# elka.net
KiCad netlist of a schematic drawn in EAGLE
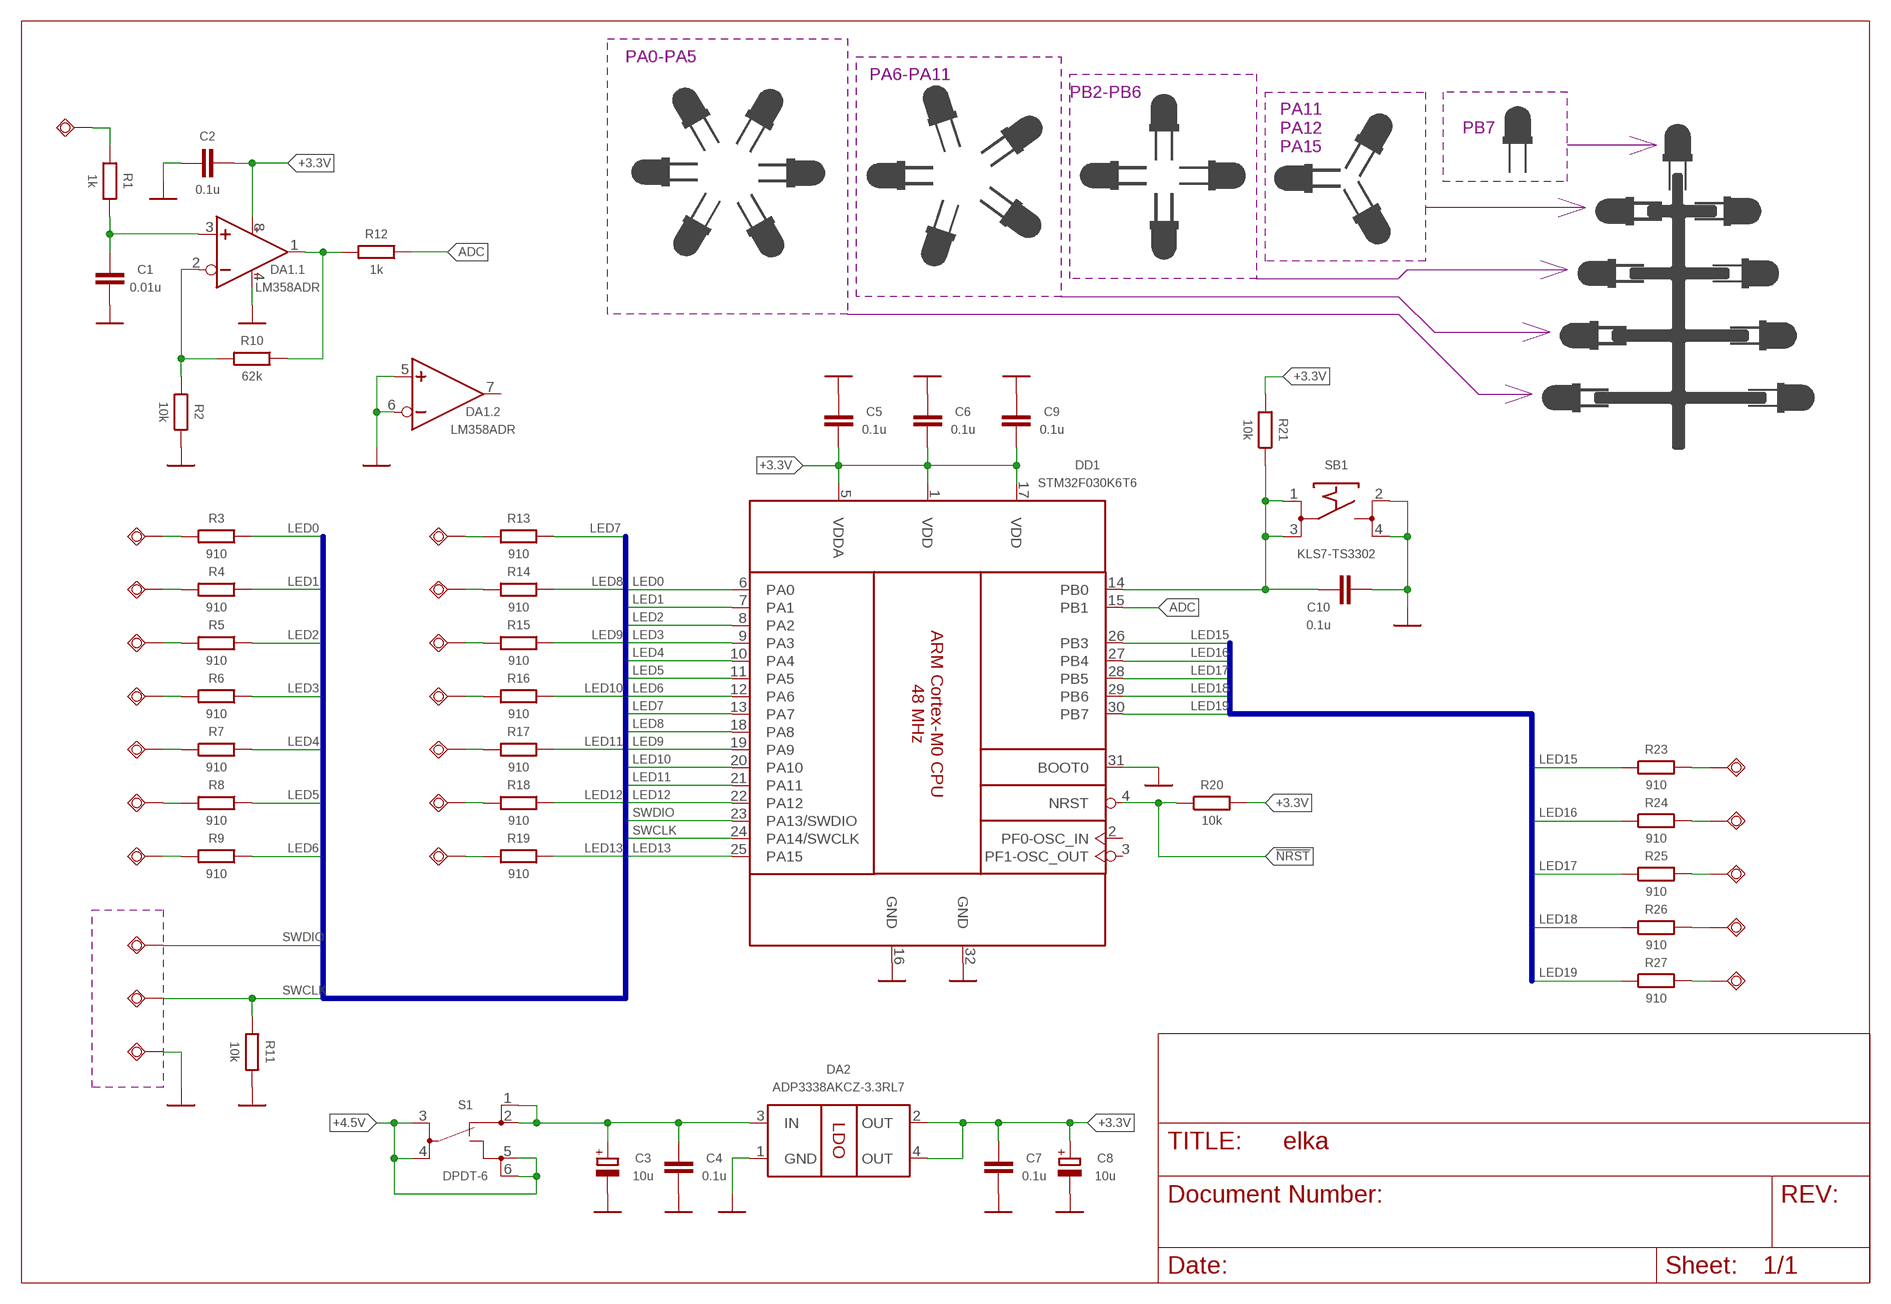
[diagram p0: schematic, sheet 1]

(export (version "E")
  (design (tool "Eeschema 10.0.6"))
  (components
    (comp (ref "C1")
      (value "0.01u")
      (footprint "eagle-import:SMD0603")
      (libsource (lib "eagle-import") (part "C0603"))
    )
    (comp (ref "C2")
      (value "0.1u")
      (footprint "eagle-import:SMD0603")
      (libsource (lib "eagle-import") (part "C0603"))
    )
    (comp (ref "C3")
      (value "10u")
      (footprint "eagle-import:SMC_B")
      (libsource (lib "eagle-import") (part "CPOLSMC_B"))
    )
    (comp (ref "C4")
      (value "0.1u")
      (footprint "eagle-import:SMD0603")
      (libsource (lib "eagle-import") (part "C0603"))
    )
    (comp (ref "C5")
      (value "0.1u")
      (footprint "eagle-import:SMD0603")
      (libsource (lib "eagle-import") (part "C0603"))
    )
    (comp (ref "C6")
      (value "0.1u")
      (footprint "eagle-import:SMD0603")
      (libsource (lib "eagle-import") (part "C0603"))
    )
    (comp (ref "C7")
      (value "0.1u")
      (footprint "eagle-import:SMD0603")
      (libsource (lib "eagle-import") (part "C0603"))
    )
    (comp (ref "C8")
      (value "10u")
      (footprint "eagle-import:SMC_B")
      (libsource (lib "eagle-import") (part "CPOLSMC_B"))
    )
    (comp (ref "C9")
      (value "0.1u")
      (footprint "eagle-import:SMD0603")
      (libsource (lib "eagle-import") (part "C0603"))
    )
    (comp (ref "C10")
      (value "0.1u")
      (footprint "eagle-import:SMD0603")
      (libsource (lib "eagle-import") (part "C0603"))
    )
    (comp (ref "DA1")
      (value "LM358ADR")
      (footprint "eagle-import:SOIC8")
      (libsource (lib "eagle-import") (part "LM358ADR"))
    )
    (comp (ref "DA2")
      (value "ADP3338AKCZ-3.3RL7")
      (footprint "eagle-import:SOT223-W")
      (libsource (lib "eagle-import") (part "ADP3338AKCZ-3.3RL7"))
    )
    (comp (ref "DD1")
      (value "STM32F030K6T6")
      (footprint "eagle-import:LQFP32")
      (libsource (lib "eagle-import") (part "STM32F030K6T6"))
    )
    (comp (ref "R1")
      (value "1k")
      (footprint "eagle-import:SMD0603")
      (libsource (lib "eagle-import") (part "R0603"))
    )
    (comp (ref "R2")
      (value "10k")
      (footprint "eagle-import:SMD0603")
      (libsource (lib "eagle-import") (part "R0603"))
    )
    (comp (ref "R3")
      (value "910")
      (footprint "eagle-import:SMD0603")
      (libsource (lib "eagle-import") (part "R0603"))
    )
    (comp (ref "R4")
      (value "910")
      (footprint "eagle-import:SMD0603")
      (libsource (lib "eagle-import") (part "R0603"))
    )
    (comp (ref "R5")
      (value "910")
      (footprint "eagle-import:SMD0603")
      (libsource (lib "eagle-import") (part "R0603"))
    )
    (comp (ref "R6")
      (value "910")
      (footprint "eagle-import:SMD0603")
      (libsource (lib "eagle-import") (part "R0603"))
    )
    (comp (ref "R7")
      (value "910")
      (footprint "eagle-import:SMD0603")
      (libsource (lib "eagle-import") (part "R0603"))
    )
    (comp (ref "R8")
      (value "910")
      (footprint "eagle-import:SMD0603")
      (libsource (lib "eagle-import") (part "R0603"))
    )
    (comp (ref "R9")
      (value "910")
      (footprint "eagle-import:SMD0603")
      (libsource (lib "eagle-import") (part "R0603"))
    )
    (comp (ref "R10")
      (value "62k")
      (footprint "eagle-import:SMD0603")
      (libsource (lib "eagle-import") (part "R0603"))
    )
    (comp (ref "R11")
      (value "10k")
      (footprint "eagle-import:SMD0603")
      (libsource (lib "eagle-import") (part "R0603"))
    )
    (comp (ref "R12")
      (value "1k")
      (footprint "eagle-import:SMD0603")
      (libsource (lib "eagle-import") (part "R0603"))
    )
    (comp (ref "R13")
      (value "910")
      (footprint "eagle-import:SMD0603")
      (libsource (lib "eagle-import") (part "R0603"))
    )
    (comp (ref "R14")
      (value "910")
      (footprint "eagle-import:SMD0603")
      (libsource (lib "eagle-import") (part "R0603"))
    )
    (comp (ref "R15")
      (value "910")
      (footprint "eagle-import:SMD0603")
      (libsource (lib "eagle-import") (part "R0603"))
    )
    (comp (ref "R16")
      (value "910")
      (footprint "eagle-import:SMD0603")
      (libsource (lib "eagle-import") (part "R0603"))
    )
    (comp (ref "R17")
      (value "910")
      (footprint "eagle-import:SMD0603")
      (libsource (lib "eagle-import") (part "R0603"))
    )
    (comp (ref "R18")
      (value "910")
      (footprint "eagle-import:SMD0603")
      (libsource (lib "eagle-import") (part "R0603"))
    )
    (comp (ref "R19")
      (value "910")
      (footprint "eagle-import:SMD0603")
      (libsource (lib "eagle-import") (part "R0603"))
    )
    (comp (ref "R20")
      (value "10k")
      (footprint "eagle-import:SMD0603")
      (libsource (lib "eagle-import") (part "R0603"))
    )
    (comp (ref "R21")
      (value "10k")
      (footprint "eagle-import:SMD0603")
      (libsource (lib "eagle-import") (part "R0603"))
    )
    (comp (ref "R23")
      (value "910")
      (footprint "eagle-import:SMD0603")
      (libsource (lib "eagle-import") (part "R0603"))
    )
    (comp (ref "R24")
      (value "910")
      (footprint "eagle-import:SMD0603")
      (libsource (lib "eagle-import") (part "R0603"))
    )
    (comp (ref "R25")
      (value "910")
      (footprint "eagle-import:SMD0603")
      (libsource (lib "eagle-import") (part "R0603"))
    )
    (comp (ref "R26")
      (value "910")
      (footprint "eagle-import:SMD0603")
      (libsource (lib "eagle-import") (part "R0603"))
    )
    (comp (ref "R27")
      (value "910")
      (footprint "eagle-import:SMD0603")
      (libsource (lib "eagle-import") (part "R0603"))
    )
    (comp (ref "S1")
      (value "DPDT-6")
      (footprint "eagle-import:DPDT")
      (libsource (lib "eagle-import") (part "DPDT-6"))
    )
    (comp (ref "SB1")
      (value "KLS7-TS3302")
      (footprint "eagle-import:KLS7-TS3302")
      (libsource (lib "eagle-import") (part "KLS7-TS3302"))
    )
    (comp (ref "TP1")
      (value "TPSQTP20R")
      (footprint "eagle-import:TP20R")
      (libsource (lib "eagle-import") (part "TPSQTP20R"))
    )
    (comp (ref "TP2")
      (value "TPSQTP20R")
      (footprint "eagle-import:TP20R")
      (libsource (lib "eagle-import") (part "TPSQTP20R"))
    )
    (comp (ref "TP3")
      (value "TPSQTP20R")
      (footprint "eagle-import:TP20R")
      (libsource (lib "eagle-import") (part "TPSQTP20R"))
    )
    (comp (ref "TP4")
      (value "TPSQTP20R")
      (footprint "eagle-import:TP20R")
      (libsource (lib "eagle-import") (part "TPSQTP20R"))
    )
    (comp (ref "TP5")
      (value "TPSQTP20R")
      (footprint "eagle-import:TP20R")
      (libsource (lib "eagle-import") (part "TPSQTP20R"))
    )
    (comp (ref "TP6")
      (value "TPSQTP20R")
      (footprint "eagle-import:TP20R")
      (libsource (lib "eagle-import") (part "TPSQTP20R"))
    )
    (comp (ref "TP7")
      (value "TPSQTP20R")
      (footprint "eagle-import:TP20R")
      (libsource (lib "eagle-import") (part "TPSQTP20R"))
    )
    (comp (ref "TP8")
      (value "TPSQTP20R")
      (footprint "eagle-import:TP20R")
      (libsource (lib "eagle-import") (part "TPSQTP20R"))
    )
    (comp (ref "TP9")
      (value "TPSQTP20R")
      (footprint "eagle-import:TP20R")
      (libsource (lib "eagle-import") (part "TPSQTP20R"))
    )
    (comp (ref "TP10")
      (value "TPSQTP20R")
      (footprint "eagle-import:TP20R")
      (libsource (lib "eagle-import") (part "TPSQTP20R"))
    )
    (comp (ref "TP11")
      (value "TPSQTP20R")
      (footprint "eagle-import:TP20R")
      (libsource (lib "eagle-import") (part "TPSQTP20R"))
    )
    (comp (ref "TP12")
      (value "TPSQTP20R")
      (footprint "eagle-import:TP20R")
      (libsource (lib "eagle-import") (part "TPSQTP20R"))
    )
    (comp (ref "TP13")
      (value "TPSQTP20R")
      (footprint "eagle-import:TP20R")
      (libsource (lib "eagle-import") (part "TPSQTP20R"))
    )
    (comp (ref "TP14")
      (value "TPSQTP20R")
      (footprint "eagle-import:TP20R")
      (libsource (lib "eagle-import") (part "TPSQTP20R"))
    )
    (comp (ref "TP15")
      (value "TPSQTP20R")
      (footprint "eagle-import:TP20R")
      (libsource (lib "eagle-import") (part "TPSQTP20R"))
    )
    (comp (ref "TP16")
      (value "TPSQTP20R")
      (footprint "eagle-import:TP20R")
      (libsource (lib "eagle-import") (part "TPSQTP20R"))
    )
    (comp (ref "TP17")
      (value "TPSQTP20R")
      (footprint "eagle-import:TP20R")
      (libsource (lib "eagle-import") (part "TPSQTP20R"))
    )
    (comp (ref "TP19")
      (value "TPSQTP20R")
      (footprint "eagle-import:TP20R")
      (libsource (lib "eagle-import") (part "TPSQTP20R"))
    )
    (comp (ref "TP20")
      (value "TPSQTP20R")
      (footprint "eagle-import:TP20R")
      (libsource (lib "eagle-import") (part "TPSQTP20R"))
    )
    (comp (ref "TP21")
      (value "TPSQTP20R")
      (footprint "eagle-import:TP20R")
      (libsource (lib "eagle-import") (part "TPSQTP20R"))
    )
    (comp (ref "TP22")
      (value "TPSQTP20R")
      (footprint "eagle-import:TP20R")
      (libsource (lib "eagle-import") (part "TPSQTP20R"))
    )
    (comp (ref "TP23")
      (value "TPSQTP20R")
      (footprint "eagle-import:TP20R")
      (libsource (lib "eagle-import") (part "TPSQTP20R"))
    )
    (comp (ref "TP24")
      (value "TPSQTP20R")
      (footprint "eagle-import:TP20R")
      (libsource (lib "eagle-import") (part "TPSQTP20R"))
    )
  )
  (nets
    (net (code "1") (name "+3.3V") (class "Default")
      (node (ref "C2") (pin "2") (pinfunction "2_2") (pintype "passive"))
      (node (ref "C5") (pin "2") (pinfunction "2_2") (pintype "passive"))
      (node (ref "C6") (pin "2") (pinfunction "2_2") (pintype "passive"))
      (node (ref "C7") (pin "1") (pinfunction "1_1") (pintype "passive"))
      (node (ref "C8") (pin "+") (pinfunction "+_+") (pintype "passive"))
      (node (ref "C9") (pin "2") (pinfunction "2_2") (pintype "passive"))
      (node (ref "DA1") (pin "8") (pinfunction "VCC+_8") (pintype "power_in"))
      (node (ref "DA2") (pin "2") (pinfunction "OUT_2") (pintype "power_in"))
      (node (ref "DA2") (pin "4") (pinfunction "OUT_4") (pintype "power_in"))
      (node (ref "DD1") (pin "1") (pinfunction "VDD_1") (pintype "power_in"))
      (node (ref "DD1") (pin "17") (pinfunction "VDD_17") (pintype "power_in"))
      (node (ref "DD1") (pin "5") (pinfunction "VDDA_5") (pintype "power_in"))
      (node (ref "R20") (pin "2") (pinfunction "2_2") (pintype "passive"))
      (node (ref "R21") (pin "2") (pinfunction "2_2") (pintype "passive"))
    )
    (net (code "2") (name "+4.5V") (class "Default")
      (node (ref "S1") (pin "3") (pinfunction "3_3") (pintype "passive"))
      (node (ref "S1") (pin "4") (pinfunction "4_4") (pintype "passive"))
      (node (ref "S1") (pin "5") (pinfunction "5_5") (pintype "passive"))
      (node (ref "S1") (pin "6") (pinfunction "6_6") (pintype "passive"))
    )
    (net (code "3") (name "/LED0") (class "Default")
      (node (ref "DD1") (pin "6") (pinfunction "PA0_6") (pintype "bidirectional"))
      (node (ref "R3") (pin "1") (pinfunction "1_1") (pintype "passive"))
    )
    (net (code "4") (name "/LED1") (class "Default")
      (node (ref "DD1") (pin "7") (pinfunction "PA1_7") (pintype "bidirectional"))
      (node (ref "R4") (pin "1") (pinfunction "1_1") (pintype "passive"))
    )
    (net (code "5") (name "/LED2") (class "Default")
      (node (ref "DD1") (pin "8") (pinfunction "PA2_8") (pintype "bidirectional"))
      (node (ref "R5") (pin "1") (pinfunction "1_1") (pintype "passive"))
    )
    (net (code "6") (name "/LED3") (class "Default")
      (node (ref "DD1") (pin "9") (pinfunction "PA3_9") (pintype "bidirectional"))
      (node (ref "R6") (pin "1") (pinfunction "1_1") (pintype "passive"))
    )
    (net (code "7") (name "/LED4") (class "Default")
      (node (ref "DD1") (pin "10") (pinfunction "PA4_10") (pintype "bidirectional"))
      (node (ref "R7") (pin "1") (pinfunction "1_1") (pintype "passive"))
    )
    (net (code "8") (name "/LED5") (class "Default")
      (node (ref "DD1") (pin "11") (pinfunction "PA5_11") (pintype "bidirectional"))
      (node (ref "R8") (pin "1") (pinfunction "1_1") (pintype "passive"))
    )
    (net (code "9") (name "/LED6") (class "Default")
      (node (ref "DD1") (pin "12") (pinfunction "PA6_12") (pintype "bidirectional"))
      (node (ref "R9") (pin "1") (pinfunction "1_1") (pintype "passive"))
    )
    (net (code "10") (name "/LED7") (class "Default")
      (node (ref "DD1") (pin "13") (pinfunction "PA7_13") (pintype "bidirectional"))
      (node (ref "R13") (pin "1") (pinfunction "1_1") (pintype "passive"))
    )
    (net (code "11") (name "/LED8") (class "Default")
      (node (ref "DD1") (pin "18") (pinfunction "PA8_18") (pintype "bidirectional"))
      (node (ref "R14") (pin "1") (pinfunction "1_1") (pintype "passive"))
    )
    (net (code "12") (name "/LED9") (class "Default")
      (node (ref "DD1") (pin "19") (pinfunction "PA9_19") (pintype "bidirectional"))
      (node (ref "R15") (pin "1") (pinfunction "1_1") (pintype "passive"))
    )
    (net (code "13") (name "/LED10") (class "Default")
      (node (ref "DD1") (pin "20") (pinfunction "PA10_20") (pintype "bidirectional"))
      (node (ref "R16") (pin "1") (pinfunction "1_1") (pintype "passive"))
    )
    (net (code "14") (name "/LED11") (class "Default")
      (node (ref "DD1") (pin "21") (pinfunction "PA11_21") (pintype "bidirectional"))
      (node (ref "R17") (pin "1") (pinfunction "1_1") (pintype "passive"))
    )
    (net (code "15") (name "/LED12") (class "Default")
      (node (ref "DD1") (pin "22") (pinfunction "PA12_22") (pintype "bidirectional"))
      (node (ref "R18") (pin "1") (pinfunction "1_1") (pintype "passive"))
    )
    (net (code "16") (name "/LED13") (class "Default")
      (node (ref "DD1") (pin "25") (pinfunction "PA15_25") (pintype "bidirectional"))
      (node (ref "R19") (pin "1") (pinfunction "1_1") (pintype "passive"))
    )
    (net (code "17") (name "/LED15") (class "Default")
      (node (ref "DD1") (pin "26") (pinfunction "PB3_26") (pintype "bidirectional"))
      (node (ref "R23") (pin "1") (pinfunction "1_1") (pintype "passive"))
    )
    (net (code "18") (name "/LED16") (class "Default")
      (node (ref "DD1") (pin "27") (pinfunction "PB4_27") (pintype "bidirectional"))
      (node (ref "R24") (pin "1") (pinfunction "1_1") (pintype "passive"))
    )
    (net (code "19") (name "/LED17") (class "Default")
      (node (ref "DD1") (pin "28") (pinfunction "PB5_28") (pintype "bidirectional"))
      (node (ref "R25") (pin "1") (pinfunction "1_1") (pintype "passive"))
    )
    (net (code "20") (name "/LED18") (class "Default")
      (node (ref "DD1") (pin "29") (pinfunction "PB6_29") (pintype "bidirectional"))
      (node (ref "R26") (pin "1") (pinfunction "1_1") (pintype "passive"))
    )
    (net (code "21") (name "/LED19") (class "Default")
      (node (ref "DD1") (pin "30") (pinfunction "PB7_30") (pintype "bidirectional"))
      (node (ref "R27") (pin "1") (pinfunction "1_1") (pintype "passive"))
    )
    (net (code "22") (name "/SWCLK") (class "Default")
      (node (ref "DD1") (pin "24") (pinfunction "PA14/SWCLK_24") (pintype "bidirectional"))
      (node (ref "R11") (pin "1") (pinfunction "1_1") (pintype "passive"))
      (node (ref "TP8") (pin "TP") (pinfunction "TP_TP") (pintype "input"))
    )
    (net (code "23") (name "/SWDIO") (class "Default")
      (node (ref "DD1") (pin "23") (pinfunction "PA13/SWDIO_23") (pintype "bidirectional"))
      (node (ref "TP7") (pin "TP") (pinfunction "TP_TP") (pintype "input"))
    )
    (net (code "24") (name "/~{NRST}") (class "Default")
      (node (ref "DD1") (pin "4") (pinfunction "NRST_4") (pintype "input"))
      (node (ref "R20") (pin "1") (pinfunction "1_1") (pintype "passive"))
    )
    (net (code "25") (name "ADC") (class "Default")
      (node (ref "DD1") (pin "15") (pinfunction "PB1_15") (pintype "bidirectional"))
      (node (ref "R12") (pin "1") (pinfunction "1_1") (pintype "passive"))
    )
    (net (code "26") (name "GND") (class "Default")
      (node (ref "C1") (pin "2") (pinfunction "2_2") (pintype "passive"))
      (node (ref "C10") (pin "2") (pinfunction "2_2") (pintype "passive"))
      (node (ref "C2") (pin "1") (pinfunction "1_1") (pintype "passive"))
      (node (ref "C3") (pin "-") (pinfunction "-_-") (pintype "passive"))
      (node (ref "C4") (pin "2") (pinfunction "2_2") (pintype "passive"))
      (node (ref "C5") (pin "1") (pinfunction "1_1") (pintype "passive"))
      (node (ref "C6") (pin "1") (pinfunction "1_1") (pintype "passive"))
      (node (ref "C7") (pin "2") (pinfunction "2_2") (pintype "passive"))
      (node (ref "C8") (pin "-") (pinfunction "-_-") (pintype "passive"))
      (node (ref "C9") (pin "1") (pinfunction "1_1") (pintype "passive"))
      (node (ref "DA1") (pin "4") (pinfunction "VCC-_4") (pintype "power_in"))
      (node (ref "DA1") (pin "5") (pinfunction "IN+_5") (pintype "input"))
      (node (ref "DA1") (pin "6") (pinfunction "IN-_6") (pintype "input"))
      (node (ref "DA2") (pin "1") (pinfunction "GND_1") (pintype "power_in"))
      (node (ref "DD1") (pin "16") (pinfunction "GND_16") (pintype "power_in"))
      (node (ref "DD1") (pin "31") (pinfunction "BOOT0_31") (pintype "input"))
      (node (ref "DD1") (pin "32") (pinfunction "GND_32") (pintype "power_in"))
      (node (ref "R11") (pin "2") (pinfunction "2_2") (pintype "passive"))
      (node (ref "R2") (pin "1") (pinfunction "1_1") (pintype "passive"))
      (node (ref "SB1") (pin "2") (pinfunction "2_2") (pintype "passive"))
      (node (ref "SB1") (pin "4") (pinfunction "4_4") (pintype "passive"))
      (node (ref "TP1") (pin "TP") (pinfunction "TP_TP") (pintype "input"))
    )
    (net (code "27") (name "Net-(DA1A-IN+)") (class "Default")
      (node (ref "C1") (pin "1") (pinfunction "1_1") (pintype "passive"))
      (node (ref "DA1") (pin "3") (pinfunction "IN+_3") (pintype "input"))
      (node (ref "R1") (pin "1") (pinfunction "1_1") (pintype "passive"))
    )
    (net (code "28") (name "Net-(DA1A-IN-)") (class "Default")
      (node (ref "DA1") (pin "2") (pinfunction "IN-_2") (pintype "input"))
      (node (ref "R10") (pin "2") (pinfunction "2_2") (pintype "passive"))
      (node (ref "R2") (pin "2") (pinfunction "2_2") (pintype "passive"))
    )
    (net (code "29") (name "Net-(DA1A-OUT)") (class "Default")
      (node (ref "DA1") (pin "1") (pinfunction "OUT_1") (pintype "output"))
      (node (ref "R10") (pin "1") (pinfunction "1_1") (pintype "passive"))
      (node (ref "R12") (pin "2") (pinfunction "2_2") (pintype "passive"))
    )
    (net (code "30") (name "Net-(DA2-IN)") (class "Default")
      (node (ref "C3") (pin "+") (pinfunction "+_+") (pintype "passive"))
      (node (ref "C4") (pin "1") (pinfunction "1_1") (pintype "passive"))
      (node (ref "DA2") (pin "3") (pinfunction "IN_3") (pintype "power_in"))
      (node (ref "S1") (pin "1") (pinfunction "1_1") (pintype "passive"))
      (node (ref "S1") (pin "2") (pinfunction "2_2") (pintype "passive"))
    )
    (net (code "31") (name "Net-(DD1-PB0)") (class "Default")
      (node (ref "C10") (pin "1") (pinfunction "1_1") (pintype "passive"))
      (node (ref "DD1") (pin "14") (pinfunction "PB0_14") (pintype "bidirectional"))
      (node (ref "R21") (pin "1") (pinfunction "1_1") (pintype "passive"))
      (node (ref "SB1") (pin "1") (pinfunction "1_1") (pintype "passive"))
      (node (ref "SB1") (pin "3") (pinfunction "3_3") (pintype "passive"))
    )
    (net (code "32") (name "Net-(R1-Pad2)") (class "Default")
      (node (ref "R1") (pin "2") (pinfunction "2_2") (pintype "passive"))
      (node (ref "TP24") (pin "TP") (pinfunction "TP_TP") (pintype "input"))
    )
    (net (code "33") (name "Net-(R3-Pad2)") (class "Default")
      (node (ref "R3") (pin "2") (pinfunction "2_2") (pintype "passive"))
      (node (ref "TP10") (pin "TP") (pinfunction "TP_TP") (pintype "input"))
    )
    (net (code "34") (name "Net-(R4-Pad2)") (class "Default")
      (node (ref "R4") (pin "2") (pinfunction "2_2") (pintype "passive"))
      (node (ref "TP11") (pin "TP") (pinfunction "TP_TP") (pintype "input"))
    )
    (net (code "35") (name "Net-(R5-Pad2)") (class "Default")
      (node (ref "R5") (pin "2") (pinfunction "2_2") (pintype "passive"))
      (node (ref "TP12") (pin "TP") (pinfunction "TP_TP") (pintype "input"))
    )
    (net (code "36") (name "Net-(R6-Pad2)") (class "Default")
      (node (ref "R6") (pin "2") (pinfunction "2_2") (pintype "passive"))
      (node (ref "TP13") (pin "TP") (pinfunction "TP_TP") (pintype "input"))
    )
    (net (code "37") (name "Net-(R7-Pad2)") (class "Default")
      (node (ref "R7") (pin "2") (pinfunction "2_2") (pintype "passive"))
      (node (ref "TP14") (pin "TP") (pinfunction "TP_TP") (pintype "input"))
    )
    (net (code "38") (name "Net-(R8-Pad2)") (class "Default")
      (node (ref "R8") (pin "2") (pinfunction "2_2") (pintype "passive"))
      (node (ref "TP15") (pin "TP") (pinfunction "TP_TP") (pintype "input"))
    )
    (net (code "39") (name "Net-(R9-Pad2)") (class "Default")
      (node (ref "R9") (pin "2") (pinfunction "2_2") (pintype "passive"))
      (node (ref "TP16") (pin "TP") (pinfunction "TP_TP") (pintype "input"))
    )
    (net (code "40") (name "Net-(R13-Pad2)") (class "Default")
      (node (ref "R13") (pin "2") (pinfunction "2_2") (pintype "passive"))
      (node (ref "TP17") (pin "TP") (pinfunction "TP_TP") (pintype "input"))
    )
    (net (code "41") (name "Net-(R14-Pad2)") (class "Default")
      (node (ref "R14") (pin "2") (pinfunction "2_2") (pintype "passive"))
      (node (ref "TP2") (pin "TP") (pinfunction "TP_TP") (pintype "input"))
    )
    (net (code "42") (name "Net-(R15-Pad2)") (class "Default")
      (node (ref "R15") (pin "2") (pinfunction "2_2") (pintype "passive"))
      (node (ref "TP3") (pin "TP") (pinfunction "TP_TP") (pintype "input"))
    )
    (net (code "43") (name "Net-(R16-Pad2)") (class "Default")
      (node (ref "R16") (pin "2") (pinfunction "2_2") (pintype "passive"))
      (node (ref "TP4") (pin "TP") (pinfunction "TP_TP") (pintype "input"))
    )
    (net (code "44") (name "Net-(R17-Pad2)") (class "Default")
      (node (ref "R17") (pin "2") (pinfunction "2_2") (pintype "passive"))
      (node (ref "TP5") (pin "TP") (pinfunction "TP_TP") (pintype "input"))
    )
    (net (code "45") (name "Net-(R18-Pad2)") (class "Default")
      (node (ref "R18") (pin "2") (pinfunction "2_2") (pintype "passive"))
      (node (ref "TP6") (pin "TP") (pinfunction "TP_TP") (pintype "input"))
    )
    (net (code "46") (name "Net-(R19-Pad2)") (class "Default")
      (node (ref "R19") (pin "2") (pinfunction "2_2") (pintype "passive"))
      (node (ref "TP9") (pin "TP") (pinfunction "TP_TP") (pintype "input"))
    )
    (net (code "47") (name "Net-(R23-Pad2)") (class "Default")
      (node (ref "R23") (pin "2") (pinfunction "2_2") (pintype "passive"))
      (node (ref "TP19") (pin "TP") (pinfunction "TP_TP") (pintype "input"))
    )
    (net (code "48") (name "Net-(R24-Pad2)") (class "Default")
      (node (ref "R24") (pin "2") (pinfunction "2_2") (pintype "passive"))
      (node (ref "TP20") (pin "TP") (pinfunction "TP_TP") (pintype "input"))
    )
    (net (code "49") (name "Net-(R25-Pad2)") (class "Default")
      (node (ref "R25") (pin "2") (pinfunction "2_2") (pintype "passive"))
      (node (ref "TP21") (pin "TP") (pinfunction "TP_TP") (pintype "input"))
    )
    (net (code "50") (name "Net-(R26-Pad2)") (class "Default")
      (node (ref "R26") (pin "2") (pinfunction "2_2") (pintype "passive"))
      (node (ref "TP22") (pin "TP") (pinfunction "TP_TP") (pintype "input"))
    )
    (net (code "51") (name "Net-(R27-Pad2)") (class "Default")
      (node (ref "R27") (pin "2") (pinfunction "2_2") (pintype "passive"))
      (node (ref "TP23") (pin "TP") (pinfunction "TP_TP") (pintype "input"))
    )
    (net (code "52") (name "unconnected-(DA1B-OUT-Pad7)") (class "Default")
      (node (ref "DA1") (pin "7") (pinfunction "OUT_7") (pintype "output"))
    )
    (net (code "53") (name "unconnected-(DD1-PF0-OSC_IN-Pad2)") (class "Default")
      (node (ref "DD1") (pin "2") (pinfunction "PF0-OSC_IN_2") (pintype "input"))
    )
    (net (code "54") (name "unconnected-(DD1-PF1-OSC_OUT-Pad3)") (class "Default")
      (node (ref "DD1") (pin "3") (pinfunction "PF1-OSC_OUT_3") (pintype "input"))
    )
  )
)
